# LazerSensors.net
KiCad netlist of a schematic drawn in Altium Designer
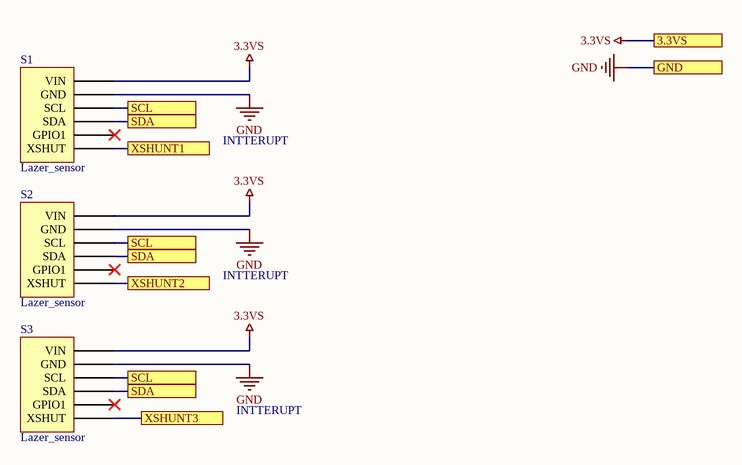
[diagram p0: LazerSensors.SchDoc]

(export (version "E")
  (design (tool "Eeschema 10.0.6"))
  (components
    (comp (ref "S1")
      (value "Lazer_sensor")
      (footprint "Lazer_Sensor")
      (description "VL53L0X (ToF-F) 940nm GY-VL53L0XV2 I2C")
      (libsource (lib "Micromouse_Schlib1") (part "Lazer_sensor"))
    )
    (comp (ref "S2")
      (value "Lazer_sensor")
      (footprint "Lazer_Sensor")
      (description "VL53L0X (ToF-F) 940nm GY-VL53L0XV2 I2C")
      (libsource (lib "Micromouse_Schlib1") (part "Lazer_sensor"))
    )
    (comp (ref "S3")
      (value "Lazer_sensor")
      (footprint "Lazer_Sensor")
      (description "VL53L0X (ToF-F) 940nm GY-VL53L0XV2 I2C")
      (libsource (lib "Micromouse_Schlib1") (part "Lazer_sensor"))
    )
  )
  (nets
    (net (code "1") (name "/SCL") (class "Default")
      (node (ref "S1") (pin "3") (pinfunction "SCL_3") (pintype "passive"))
      (node (ref "S2") (pin "3") (pinfunction "SCL_3") (pintype "passive"))
      (node (ref "S3") (pin "3") (pinfunction "SCL_3") (pintype "passive"))
    )
    (net (code "2") (name "/SDA") (class "Default")
      (node (ref "S1") (pin "4") (pinfunction "SDA_4") (pintype "passive"))
      (node (ref "S2") (pin "4") (pinfunction "SDA_4") (pintype "passive"))
      (node (ref "S3") (pin "4") (pinfunction "SDA_4") (pintype "passive"))
    )
    (net (code "3") (name "/XSHUNT1") (class "Default")
      (node (ref "S1") (pin "6") (pinfunction "XSHUT_6") (pintype "passive"))
    )
    (net (code "4") (name "/XSHUNT2") (class "Default")
      (node (ref "S2") (pin "6") (pinfunction "XSHUT_6") (pintype "passive"))
    )
    (net (code "5") (name "/XSHUNT3") (class "Default")
      (node (ref "S3") (pin "6") (pinfunction "XSHUT_6") (pintype "passive"))
    )
    (net (code "6") (name "3.3VS") (class "Default")
      (node (ref "S1") (pin "1") (pinfunction "VIN_1") (pintype "passive"))
      (node (ref "S2") (pin "1") (pinfunction "VIN_1") (pintype "passive"))
      (node (ref "S3") (pin "1") (pinfunction "VIN_1") (pintype "passive"))
    )
    (net (code "7") (name "GND") (class "Default")
      (node (ref "S1") (pin "2") (pinfunction "GND_2") (pintype "passive"))
      (node (ref "S2") (pin "2") (pinfunction "GND_2") (pintype "passive"))
      (node (ref "S3") (pin "2") (pinfunction "GND_2") (pintype "passive"))
    )
    (net (code "8") (name "unconnected-(S1-GPIO1-Pad5)") (class "Default")
      (node (ref "S1") (pin "5") (pinfunction "GPIO1_5") (pintype "passive+no_connect"))
    )
    (net (code "9") (name "unconnected-(S2-GPIO1-Pad5)") (class "Default")
      (node (ref "S2") (pin "5") (pinfunction "GPIO1_5") (pintype "passive+no_connect"))
    )
    (net (code "10") (name "unconnected-(S3-GPIO1-Pad5)") (class "Default")
      (node (ref "S3") (pin "5") (pinfunction "GPIO1_5") (pintype "passive+no_connect"))
    )
  )
)
